# STM32_MCU.net
KiCad netlist of a schematic drawn in Altium Designer
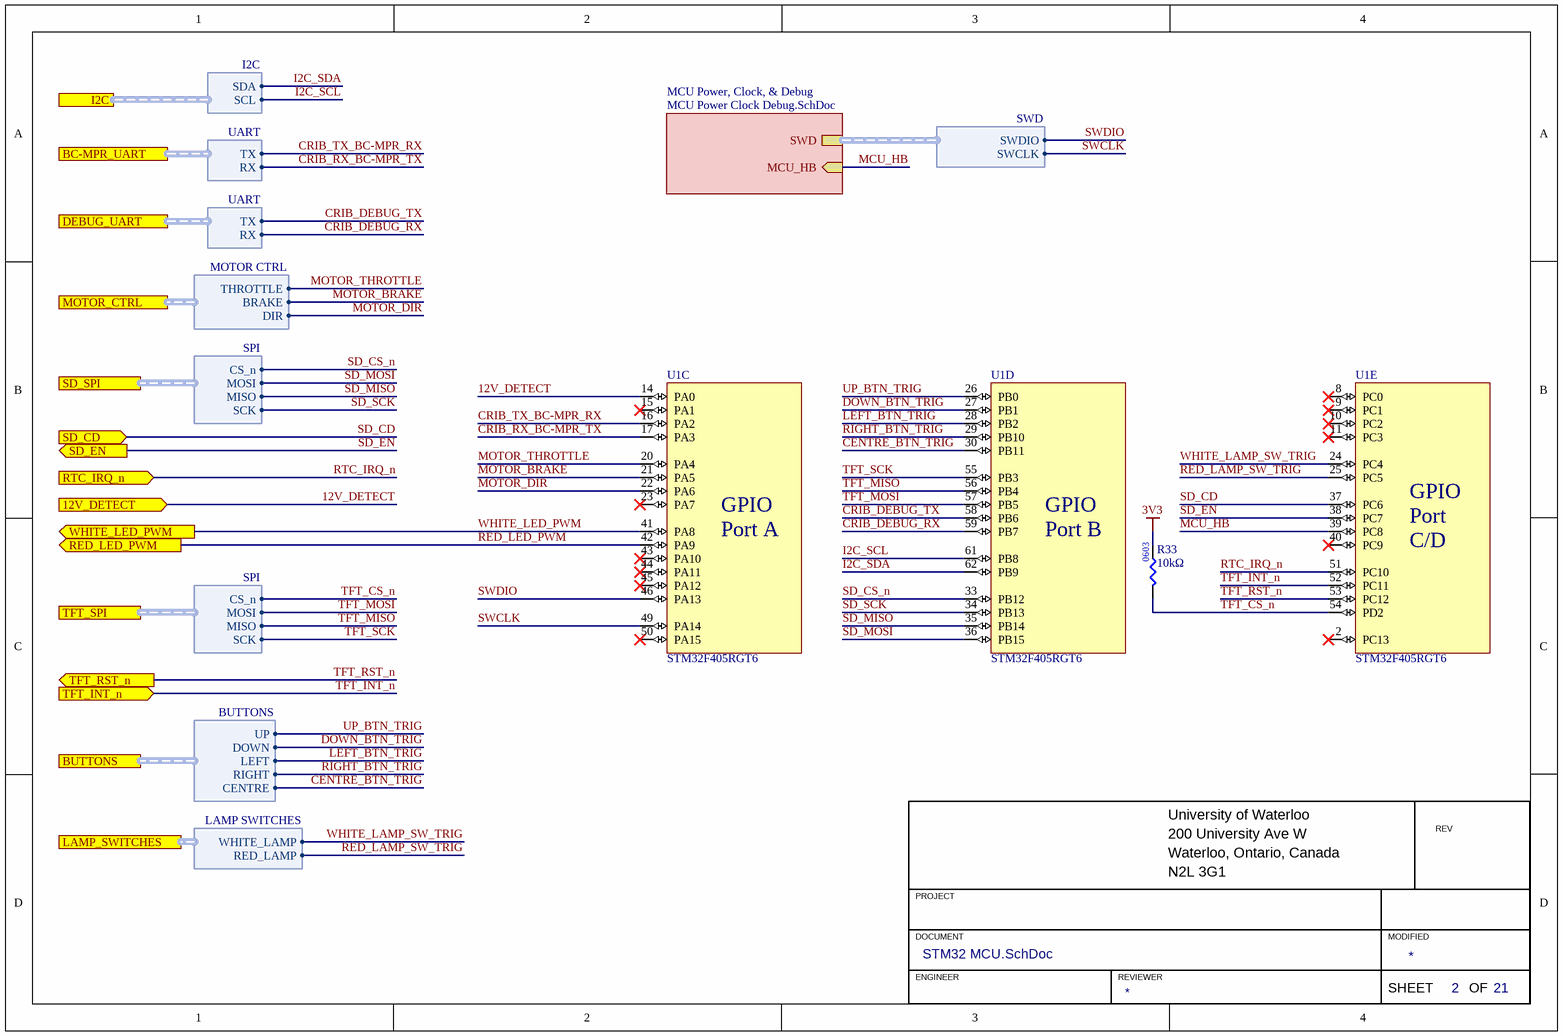
[diagram p0: STM32 MCU.SchDoc]

(export (version "E")
  (design (tool "Eeschema 10.0.6"))
  (components
    (comp (ref "R33")
      (value "10kΩ")
      (footprint "RES0603")
      (description "RES 10K OHM 1% 1/8W 0603")
      (fields (field (name "Comment") "RES_10kΩ_0603_1%"))
      (libsource (lib "Personal_Schematic_Library_2022") (part "RES_10kΩ_0603_1%"))
    )
    (comp (ref "U1")
      (value "STM32F405RGT6")
      (footprint "STM_LQFP64")
      (description "IC MCU 32BIT 1MB FLASH 64LQFP")
      (libsource (lib "Personal_Schematic_Library_2022") (part "STM32F405RGT6"))
    )
  )
  (nets
    (net (code "10") (name "/12V_DETECT") (class "Default")
      (node (ref "U1") (pin "14") (pinfunction "PA0_14") (pintype "bidirectional"))
    )
    (net (code "11") (name "/CENTRE_BTN_TRIG") (class "Default")
      (node (ref "U1") (pin "30") (pinfunction "PB11_30") (pintype "bidirectional"))
    )
    (net (code "12") (name "/CRIB_DEBUG_RX") (class "Default")
      (node (ref "U1") (pin "59") (pinfunction "PB7_59") (pintype "bidirectional"))
    )
    (net (code "13") (name "/CRIB_DEBUG_TX") (class "Default")
      (node (ref "U1") (pin "58") (pinfunction "PB6_58") (pintype "bidirectional"))
    )
    (net (code "14") (name "/CRIB_RX_BC-MPR_TX") (class "Default")
      (node (ref "U1") (pin "17") (pinfunction "PA3_17") (pintype "bidirectional"))
    )
    (net (code "15") (name "/CRIB_TX_BC-MPR_RX") (class "Default")
      (node (ref "U1") (pin "16") (pinfunction "PA2_16") (pintype "bidirectional"))
    )
    (net (code "16") (name "/DOWN_BTN_TRIG") (class "Default")
      (node (ref "U1") (pin "27") (pinfunction "PB1_27") (pintype "bidirectional"))
    )
    (net (code "17") (name "/I2C_SCL") (class "Default")
      (node (ref "U1") (pin "61") (pinfunction "PB8_61") (pintype "bidirectional"))
    )
    (net (code "18") (name "/I2C_SDA") (class "Default")
      (node (ref "U1") (pin "62") (pinfunction "PB9_62") (pintype "bidirectional"))
    )
    (net (code "19") (name "/LEFT_BTN_TRIG") (class "Default")
      (node (ref "U1") (pin "28") (pinfunction "PB2_28") (pintype "bidirectional"))
    )
    (net (code "20") (name "/MCU_HB") (class "Default")
      (node (ref "U1") (pin "39") (pinfunction "PC8_39") (pintype "bidirectional"))
    )
    (net (code "21") (name "/MOTOR_BRAKE") (class "Default")
      (node (ref "U1") (pin "21") (pinfunction "PA5_21") (pintype "bidirectional"))
    )
    (net (code "22") (name "/MOTOR_DIR") (class "Default")
      (node (ref "U1") (pin "22") (pinfunction "PA6_22") (pintype "bidirectional"))
    )
    (net (code "23") (name "/MOTOR_THROTTLE") (class "Default")
      (node (ref "U1") (pin "20") (pinfunction "PA4_20") (pintype "bidirectional"))
    )
    (net (code "24") (name "/RED_LAMP_SW_TRIG") (class "Default")
      (node (ref "U1") (pin "25") (pinfunction "PC5_25") (pintype "bidirectional"))
    )
    (net (code "25") (name "/RED_LED_PWM") (class "Default")
      (node (ref "U1") (pin "42") (pinfunction "PA9_42") (pintype "bidirectional"))
    )
    (net (code "26") (name "/RIGHT_BTN_TRIG") (class "Default")
      (node (ref "U1") (pin "29") (pinfunction "PB10_29") (pintype "bidirectional"))
    )
    (net (code "27") (name "/RTC_IRQ_n") (class "Default")
      (node (ref "U1") (pin "51") (pinfunction "PC10_51") (pintype "bidirectional"))
    )
    (net (code "28") (name "/SD_CD") (class "Default")
      (node (ref "U1") (pin "37") (pinfunction "PC6_37") (pintype "bidirectional"))
    )
    (net (code "29") (name "/SD_CS_n") (class "Default")
      (node (ref "U1") (pin "33") (pinfunction "PB12_33") (pintype "bidirectional"))
    )
    (net (code "30") (name "/SD_EN") (class "Default")
      (node (ref "U1") (pin "38") (pinfunction "PC7_38") (pintype "bidirectional"))
    )
    (net (code "31") (name "/SD_MISO") (class "Default")
      (node (ref "U1") (pin "35") (pinfunction "PB14_35") (pintype "bidirectional"))
    )
    (net (code "32") (name "/SD_MOSI") (class "Default")
      (node (ref "U1") (pin "36") (pinfunction "PB15_36") (pintype "bidirectional"))
    )
    (net (code "33") (name "/SD_SCK") (class "Default")
      (node (ref "U1") (pin "34") (pinfunction "PB13_34") (pintype "bidirectional"))
    )
    (net (code "34") (name "/SWCLK") (class "Default")
      (node (ref "U1") (pin "49") (pinfunction "PA14_49") (pintype "bidirectional"))
    )
    (net (code "35") (name "/SWDIO") (class "Default")
      (node (ref "U1") (pin "46") (pinfunction "PA13_46") (pintype "bidirectional"))
    )
    (net (code "36") (name "/TFT_CS_n") (class "Default")
      (node (ref "R33") (pin "1") (pinfunction "1_1") (pintype "passive"))
      (node (ref "U1") (pin "54") (pinfunction "PD2_54") (pintype "bidirectional"))
    )
    (net (code "37") (name "/TFT_INT_n") (class "Default")
      (node (ref "U1") (pin "52") (pinfunction "PC11_52") (pintype "bidirectional"))
    )
    (net (code "38") (name "/TFT_MISO") (class "Default")
      (node (ref "U1") (pin "56") (pinfunction "PB4_56") (pintype "bidirectional"))
    )
    (net (code "39") (name "/TFT_MOSI") (class "Default")
      (node (ref "U1") (pin "57") (pinfunction "PB5_57") (pintype "bidirectional"))
    )
    (net (code "40") (name "/TFT_RST_n") (class "Default")
      (node (ref "U1") (pin "53") (pinfunction "PC12_53") (pintype "bidirectional"))
    )
    (net (code "41") (name "/TFT_SCK") (class "Default")
      (node (ref "U1") (pin "55") (pinfunction "PB3_55") (pintype "bidirectional"))
    )
    (net (code "42") (name "/UP_BTN_TRIG") (class "Default")
      (node (ref "U1") (pin "26") (pinfunction "PB0_26") (pintype "bidirectional"))
    )
    (net (code "43") (name "/WHITE_LAMP_SW_TRIG") (class "Default")
      (node (ref "U1") (pin "24") (pinfunction "PC4_24") (pintype "bidirectional"))
    )
    (net (code "44") (name "/WHITE_LED_PWM") (class "Default")
      (node (ref "U1") (pin "41") (pinfunction "PA8_41") (pintype "bidirectional"))
    )
    (net (code "52") (name "3V3") (class "Default")
      (node (ref "R33") (pin "2") (pinfunction "2_2") (pintype "passive"))
    )
    (net (code "53") (name "unconnected-(U1C-PA1-Pad15)") (class "Default")
      (node (ref "U1") (pin "15") (pinfunction "PA1_15") (pintype "bidirectional+no_connect"))
    )
    (net (code "54") (name "unconnected-(U1C-PA7-Pad23)") (class "Default")
      (node (ref "U1") (pin "23") (pinfunction "PA7_23") (pintype "bidirectional+no_connect"))
    )
    (net (code "55") (name "unconnected-(U1C-PA10-Pad43)") (class "Default")
      (node (ref "U1") (pin "43") (pinfunction "PA10_43") (pintype "bidirectional+no_connect"))
    )
    (net (code "56") (name "unconnected-(U1C-PA11-Pad44)") (class "Default")
      (node (ref "U1") (pin "44") (pinfunction "PA11_44") (pintype "bidirectional+no_connect"))
    )
    (net (code "57") (name "unconnected-(U1C-PA12-Pad45)") (class "Default")
      (node (ref "U1") (pin "45") (pinfunction "PA12_45") (pintype "bidirectional+no_connect"))
    )
    (net (code "58") (name "unconnected-(U1C-PA15-Pad50)") (class "Default")
      (node (ref "U1") (pin "50") (pinfunction "PA15_50") (pintype "bidirectional+no_connect"))
    )
    (net (code "59") (name "unconnected-(U1E-PC0-Pad8)") (class "Default")
      (node (ref "U1") (pin "8") (pinfunction "PC0_8") (pintype "bidirectional+no_connect"))
    )
    (net (code "60") (name "unconnected-(U1E-PC1-Pad9)") (class "Default")
      (node (ref "U1") (pin "9") (pinfunction "PC1_9") (pintype "bidirectional+no_connect"))
    )
    (net (code "61") (name "unconnected-(U1E-PC2-Pad10)") (class "Default")
      (node (ref "U1") (pin "10") (pinfunction "PC2_10") (pintype "bidirectional+no_connect"))
    )
    (net (code "62") (name "unconnected-(U1E-PC3-Pad11)") (class "Default")
      (node (ref "U1") (pin "11") (pinfunction "PC3_11") (pintype "bidirectional+no_connect"))
    )
    (net (code "63") (name "unconnected-(U1E-PC9-Pad40)") (class "Default")
      (node (ref "U1") (pin "40") (pinfunction "PC9_40") (pintype "bidirectional+no_connect"))
    )
    (net (code "64") (name "unconnected-(U1E-PC13-Pad2)") (class "Default")
      (node (ref "U1") (pin "2") (pinfunction "PC13_2") (pintype "bidirectional+no_connect"))
    )
  )
)
